# Filter_Circuit.net
KiCad netlist of a schematic drawn in Altium Designer
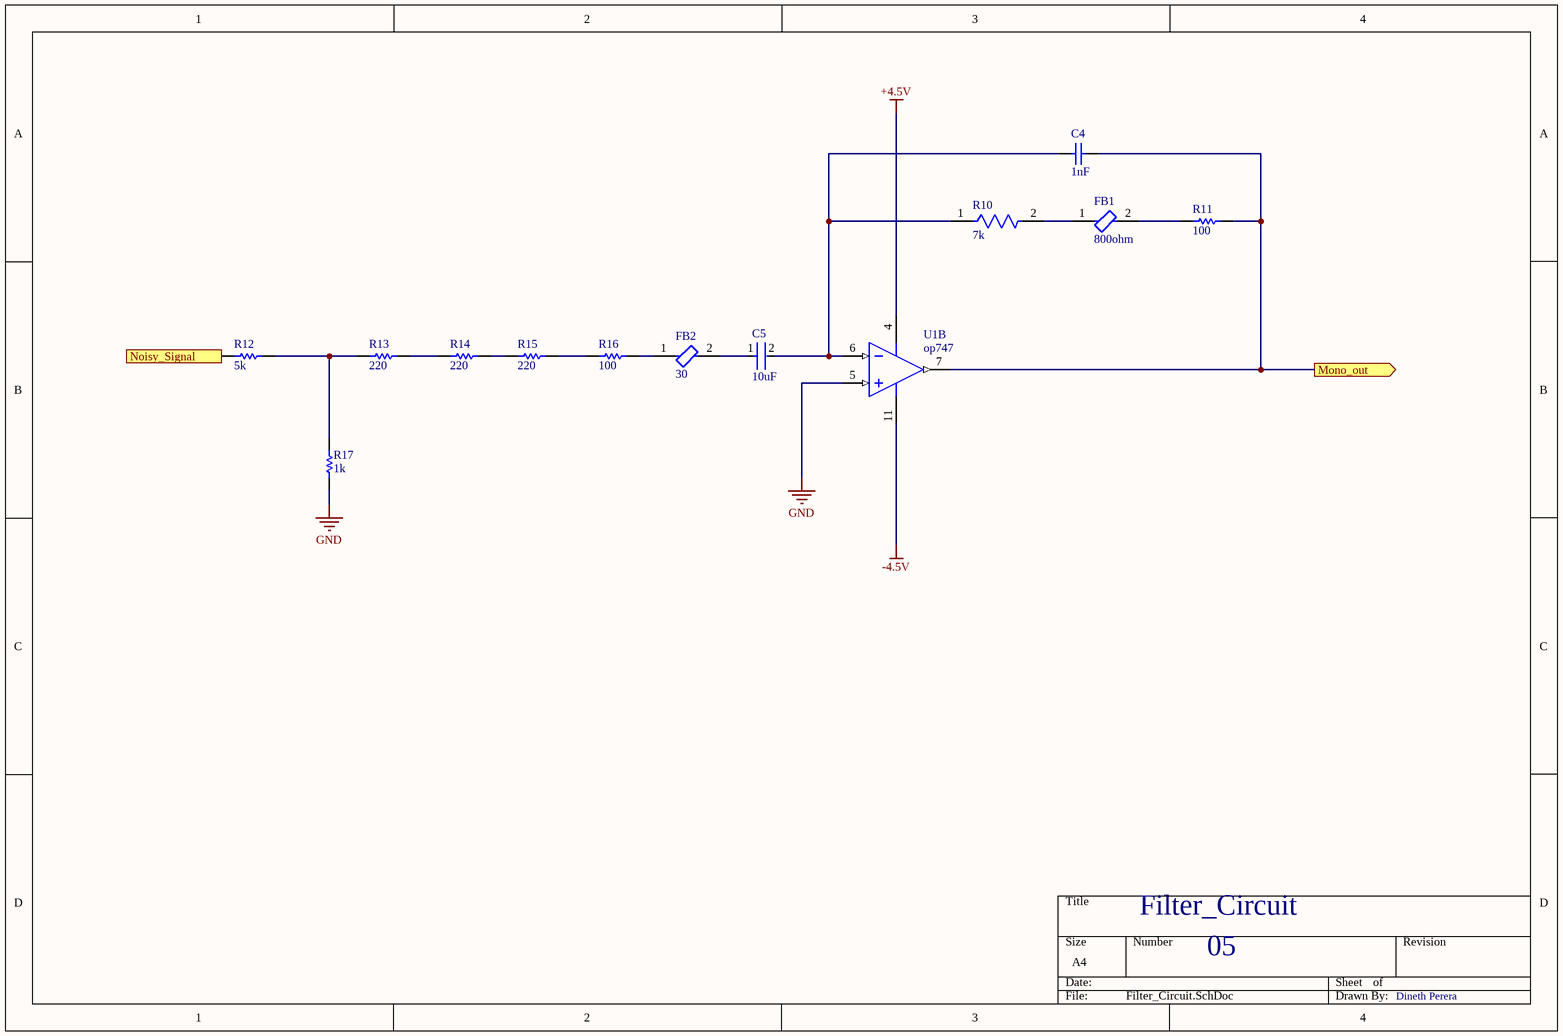
[diagram p0: Filter_Circuit.SchDoc]

(export (version "E")
  (design (tool "Eeschema 10.0.6"))
  (components
    (comp (ref "C4")
      (value "1nF")
      (footprint "CAPC1608X90X35NL10T15")
      (fields (field (name "PART NUMBER") "GRM188R71H102KA01D") (field (name "MANUFACTURER") "Murata"))
      (libsource (lib "Altium Content Vault") (part "CAP"))
    )
    (comp (ref "C5")
      (value "10uF")
      (footprint "FP-C0805C-DG-MFG")
      (description "SMD Comm X5R, Ceramic, 10 uF, 10%, 10 V, X5R, SMD, MLCC, Temperature Stable, Class II, 0805")
      (fields (field (name "TOLERANCE") "10%"))
      (libsource (lib "Altium Content Vault") (part "11868f565c42a9108669ba33697ecf6"))
    )
    (comp (ref "FB1")
      (value "800ohm")
      (footprint "FP-BLM31-0_2-t1_6-IPC_A")
      (description "Chip Ferrite Bead, 1206, 800Ω @ 100MHz, 0.05Ω, 25%, 2.5A")
      (libsource (lib "Altium Content Vault") (part "5f30dd21d616792df468990f7003faa"))
    )
    (comp (ref "FB2")
      (value "30")
      (footprint "FP-BLM21-0_2-t0_85-e0_5-d-MFG")
      (description "Chip Ferrite Bead, 0805, 30Ω @ 100MHz, 0.014Ω, , 4A")
      (fields (field (name "TOLERANCE") "25%"))
      (libsource (lib "Altium Content Vault") (part "5f30dd21d616792df468990f7003faa"))
    )
    (comp (ref "R10")
      (value "7k")
      (footprint "FP-RMCF0805-MFG")
      (description "4.7kΩ ±5% 0.125W 0805 Thick Film Chip Resistor AEC-Q200 compliant")
      (fields (field (name "TOLERANCE") "5%"))
      (libsource (lib "Altium Content Vault") (part "1029c3af85768c4190bb7ad29bc67b5"))
    )
    (comp (ref "R11")
      (value "100")
      (footprint "RESC1005X40X25LL05T05")
      (description "Chip Resistor, 100 Ohm, +/- 1%, 100 mW, -55 to 155 degC, 0402 (1005 Metric), RoHS, Tape and Reel")
      (fields (field (name "MANUFACTURER") "Basic Passives") (field (name "TOLERANCE") "1%"))
      (libsource (lib "Altium Content Vault") (part "RES-2"))
    )
    (comp (ref "R12")
      (value "5k")
      (footprint "RESC2013X50X30NL20T20")
      (fields (field (name "PART NUMBER") "CRCW08055K00FKTA") (field (name "MANUFACTURER") "Vishay Dale"))
      (libsource (lib "Altium Content Vault") (part "RES"))
    )
    (comp (ref "R13")
      (value "220")
      (footprint "RESC2013X70X40NL20T20")
      (fields (field (name "PART NUMBER") "ERJ6ENF2200V") (field (name "MANUFACTURER") "Panasonic"))
      (libsource (lib "Altium Content Vault") (part "RES"))
    )
    (comp (ref "R14")
      (value "220")
      (footprint "RESC2013X70X40NL20T20")
      (fields (field (name "PART NUMBER") "ERJ6ENF2200V") (field (name "MANUFACTURER") "Panasonic"))
      (libsource (lib "Altium Content Vault") (part "RES"))
    )
    (comp (ref "R15")
      (value "220")
      (footprint "RESC2013X70X40NL20T20")
      (fields (field (name "PART NUMBER") "ERJ6ENF2200V") (field (name "MANUFACTURER") "Panasonic"))
      (libsource (lib "Altium Content Vault") (part "RES"))
    )
    (comp (ref "R16")
      (value "100")
      (footprint "RESC2013X60X40ML20T25")
      (fields (field (name "MANUFACTURER") "Panasonic") (field (name "PART NUMBER") "ERA6AEB101V"))
      (libsource (lib "Altium Content Vault") (part "RES"))
    )
    (comp (ref "R17")
      (value "1k")
      (footprint "RESC2013X70X40LL20T20")
      (description "Chip Resistor, 1 KOhm, +/- 1%, 0.125 W, -55 to 155 degC, 0805 (2012 Metric), RoHS, Tape and Reel")
      (fields (field (name "MANUFACTURER") "Panasonic"))
      (libsource (lib "Altium Content Vault") (part "RES-2"))
    )
    (comp (ref "U1")
      (value "op747")
      (footprint "ADI-R-14_L")
      (fields
        (field (name "MANUFACTURER") "Analog Devices")
        (field (name "GENERIC PART NUMBER") "OP747")
        (field (name "PARTNUMBER") "OP747ARZ-REEL7")
      )
      (libsource (lib "Altium Content Vault") (part "ADI-ADxxxx_OPxxxx-X-14"))
    )
  )
  (nets
    (net (code "1") (name "+4.5V") (class "Default")
      (node (ref "U1") (pin "4") (pinfunction "+V_4") (pintype "power_in"))
    )
    (net (code "2") (name "-4.5V") (class "Default")
      (node (ref "U1") (pin "11") (pinfunction "-V_11") (pintype "power_in"))
    )
    (net (code "3") (name "/Mono_out") (class "Default")
      (node (ref "C4") (pin "2") (pinfunction "2_2") (pintype "passive"))
      (node (ref "R11") (pin "2") (pinfunction "2_2") (pintype "passive"))
      (node (ref "U1") (pin "7") (pinfunction "OUT_B_7") (pintype "output"))
    )
    (net (code "4") (name "/Noisy_Signal") (class "Default")
      (node (ref "R12") (pin "1") (pinfunction "1_1") (pintype "passive"))
    )
    (net (code "5") (name "GND") (class "Default")
      (node (ref "R17") (pin "1") (pinfunction "1_1") (pintype "passive"))
      (node (ref "U1") (pin "5") (pinfunction "+IN_B_5") (pintype "input"))
    )
    (net (code "6") (name "Net-(C5-Pad1)") (class "Default")
      (node (ref "C5") (pin "1") (pinfunction "1_1") (pintype "passive"))
      (node (ref "FB2") (pin "2") (pinfunction "2_2") (pintype "passive"))
    )
    (net (code "7") (name "Net-(FB1-Pad1)") (class "Default")
      (node (ref "FB1") (pin "1") (pinfunction "1_1") (pintype "passive"))
      (node (ref "R10") (pin "2") (pinfunction "2_2") (pintype "passive"))
    )
    (net (code "8") (name "Net-(FB1-Pad2)") (class "Default")
      (node (ref "FB1") (pin "2") (pinfunction "2_2") (pintype "passive"))
      (node (ref "R11") (pin "1") (pinfunction "1_1") (pintype "passive"))
    )
    (net (code "9") (name "Net-(FB2-Pad1)") (class "Default")
      (node (ref "FB2") (pin "1") (pinfunction "1_1") (pintype "passive"))
      (node (ref "R16") (pin "2") (pinfunction "2_2") (pintype "passive"))
    )
    (net (code "10") (name "Net-(R12-Pad2)") (class "Default")
      (node (ref "R12") (pin "2") (pinfunction "2_2") (pintype "passive"))
      (node (ref "R13") (pin "1") (pinfunction "1_1") (pintype "passive"))
      (node (ref "R17") (pin "2") (pinfunction "2_2") (pintype "passive"))
    )
    (net (code "11") (name "Net-(R13-Pad2)") (class "Default")
      (node (ref "R13") (pin "2") (pinfunction "2_2") (pintype "passive"))
      (node (ref "R14") (pin "1") (pinfunction "1_1") (pintype "passive"))
    )
    (net (code "12") (name "Net-(R14-Pad2)") (class "Default")
      (node (ref "R14") (pin "2") (pinfunction "2_2") (pintype "passive"))
      (node (ref "R15") (pin "1") (pinfunction "1_1") (pintype "passive"))
    )
    (net (code "13") (name "Net-(R15-Pad2)") (class "Default")
      (node (ref "R15") (pin "2") (pinfunction "2_2") (pintype "passive"))
      (node (ref "R16") (pin "1") (pinfunction "1_1") (pintype "passive"))
    )
    (net (code "14") (name "Net-(U1B--IN_B)") (class "Default")
      (node (ref "C4") (pin "1") (pinfunction "1_1") (pintype "passive"))
      (node (ref "C5") (pin "2") (pinfunction "2_2") (pintype "passive"))
      (node (ref "R10") (pin "1") (pinfunction "1_1") (pintype "passive"))
      (node (ref "U1") (pin "6") (pinfunction "-IN_B_6") (pintype "input"))
    )
  )
)
